# design.net
KiCad netlist of a schematic drawn in Altium Designer
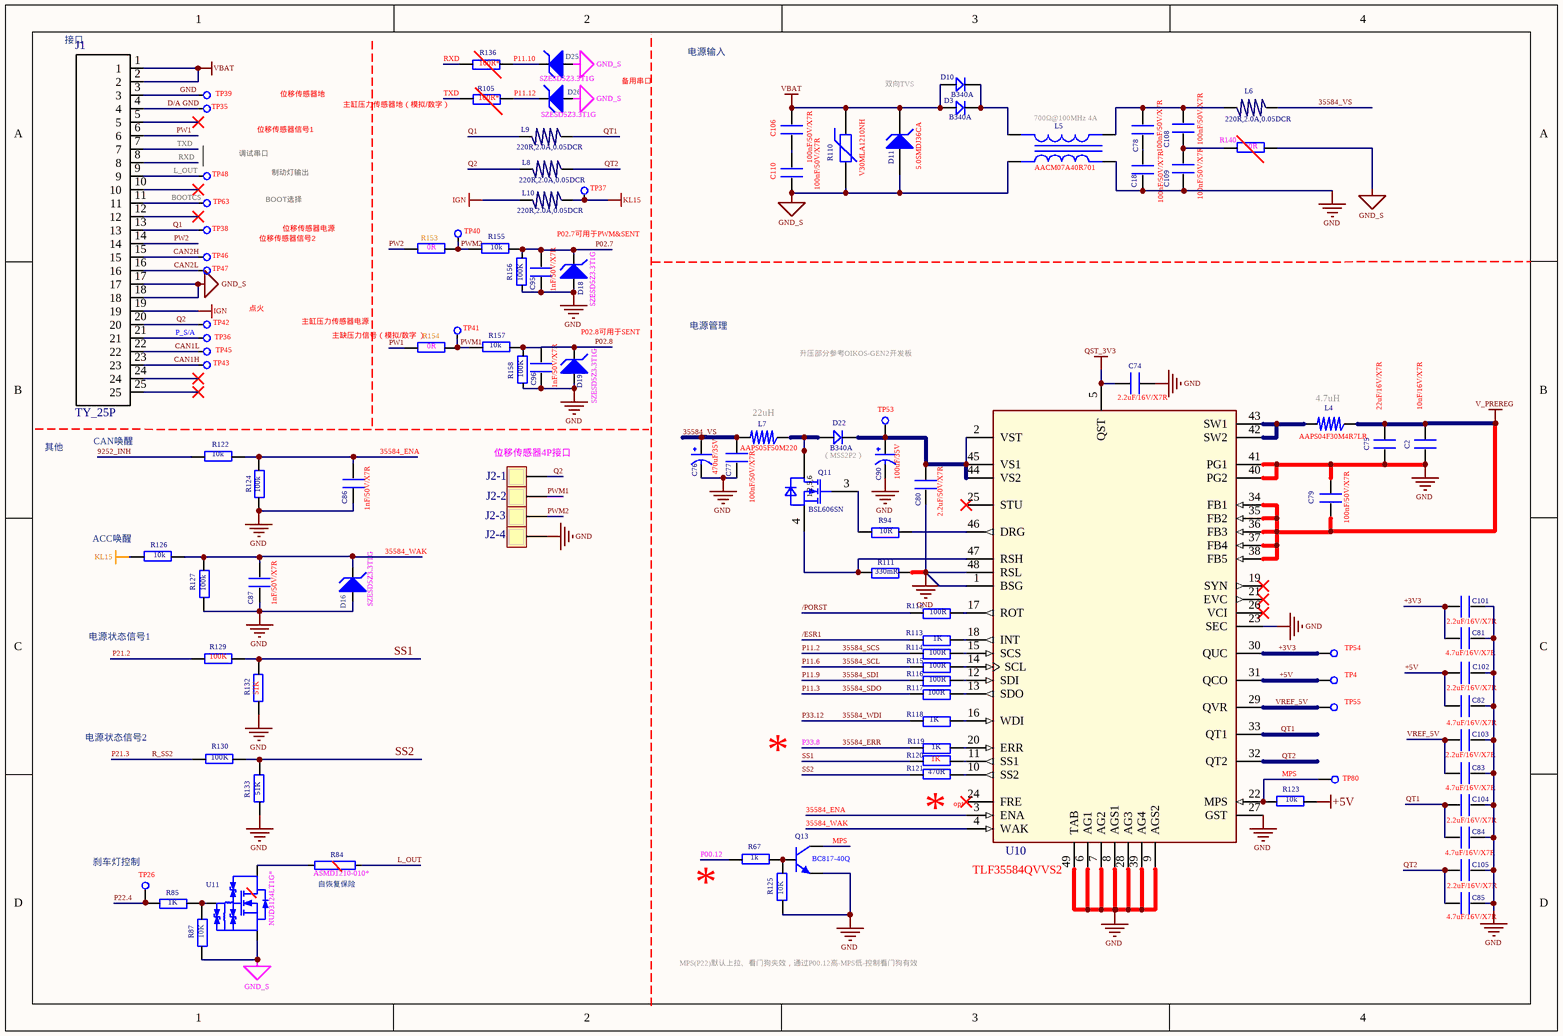
[diagram p0: 电源.SchDoc]

(export (version "E")
  (design (tool "Eeschema 10.0.6"))
  (components
    (comp (ref "C2")
      (value "10uF/16V/X7R")
      (footprint "C1206")
      (libsource (lib "WarShip V3 STM32103封装库") (part "C"))
    )
    (comp (ref "C18")
      (value "100nF/50V/X7R")
      (footprint "0805")
      (libsource (lib "WarShip V3 STM32103封装库") (part "C"))
    )
    (comp (ref "C74")
      (value "2.2uF/16V/X7R")
      (footprint "C0603P")
      (libsource (lib "WarShip V3 STM32103封装库") (part "C"))
    )
    (comp (ref "C75")
      (value "22uF/16V/X7R")
      (footprint "C1206")
      (libsource (lib "WarShip V3 STM32103封装库") (part "C"))
    )
    (comp (ref "C76")
      (value "470uF/35V")
      (footprint "CM F(10*10.2)")
      (libsource (lib "WarShip V3 STM32103封装库") (part "CAP"))
    )
    (comp (ref "C77")
      (value "100nF/50V/X7R")
      (footprint "C0603P")
      (libsource (lib "WarShip V3 STM32103封装库") (part "C"))
    )
    (comp (ref "C78")
      (value "100nF/50V/X7R")
      (footprint "0805")
      (libsource (lib "WarShip V3 STM32103封装库") (part "C"))
    )
    (comp (ref "C79")
      (value "100nF/50V/X7R")
      (footprint "C0603P")
      (libsource (lib "WarShip V3 STM32103封装库") (part "C"))
    )
    (comp (ref "C80")
      (value "2.2uF/50V/X7R")
      (footprint "C0805")
      (libsource (lib "WarShip V3 STM32103封装库") (part "C"))
    )
    (comp (ref "C81")
      (value "4.7uF/16V/X7R")
      (footprint "C0805")
      (libsource (lib "WarShip V3 STM32103封装库") (part "C"))
    )
    (comp (ref "C82")
      (value "4.7uF/16V/X7R")
      (footprint "C0805")
      (libsource (lib "WarShip V3 STM32103封装库") (part "C"))
    )
    (comp (ref "C83")
      (value "4.7uF/16V/X7R")
      (footprint "C0805")
      (libsource (lib "WarShip V3 STM32103封装库") (part "C"))
    )
    (comp (ref "C84")
      (value "4.7uF/16V/X7R")
      (footprint "C0805")
      (libsource (lib "WarShip V3 STM32103封装库") (part "C"))
    )
    (comp (ref "C85")
      (value "4.7uF/16V/X7R")
      (footprint "C0805")
      (libsource (lib "WarShip V3 STM32103封装库") (part "C"))
    )
    (comp (ref "C86")
      (value "1nF/50V/X7R")
      (footprint "C0603P")
      (libsource (lib "WarShip V3 STM32103封装库") (part "C"))
    )
    (comp (ref "C87")
      (value "1nF/50V/X7R")
      (footprint "C0603P")
      (libsource (lib "WarShip V3 STM32103封装库") (part "C"))
    )
    (comp (ref "C90")
      (value "100uF/35V")
      (footprint "AL-6.3*5.8")
      (libsource (lib "WarShip V3 STM32103封装库") (part "CAP"))
    )
    (comp (ref "C95")
      (value "1nF/50V/X7R")
      (footprint "C0603P")
      (libsource (lib "WarShip V3 STM32103封装库") (part "C"))
    )
    (comp (ref "C96")
      (value "1nF/50V/X7R")
      (footprint "C0603P")
      (libsource (lib "WarShip V3 STM32103封装库") (part "C"))
    )
    (comp (ref "C101")
      (value "2.2uF/16V/X7R")
      (footprint "C0603P")
      (libsource (lib "WarShip V3 STM32103封装库") (part "C"))
    )
    (comp (ref "C102")
      (value "2.2uF/16V/X7R")
      (footprint "C0603P")
      (libsource (lib "WarShip V3 STM32103封装库") (part "C"))
    )
    (comp (ref "C103")
      (value "2.2uF/16V/X7R")
      (footprint "C0603P")
      (libsource (lib "WarShip V3 STM32103封装库") (part "C"))
    )
    (comp (ref "C104")
      (value "2.2uF/16V/X7R")
      (footprint "C0603P")
      (libsource (lib "WarShip V3 STM32103封装库") (part "C"))
    )
    (comp (ref "C105")
      (value "2.2uF/16V/X7R")
      (footprint "C0603P")
      (libsource (lib "WarShip V3 STM32103封装库") (part "C"))
    )
    (comp (ref "C106")
      (value "100nF/50V/X7R")
      (footprint "0805")
      (libsource (lib "WarShip V3 STM32103封装库") (part "C"))
    )
    (comp (ref "C108")
      (value "100nF/50V/X7R")
      (footprint "C0805")
      (libsource (lib "WarShip V3 STM32103封装库") (part "C"))
    )
    (comp (ref "C109")
      (value "100nF/50V/X7R")
      (footprint "C0805")
      (libsource (lib "WarShip V3 STM32103封装库") (part "C"))
    )
    (comp (ref "C110")
      (value "100nF/50V/X7R")
      (footprint "0805")
      (libsource (lib "WarShip V3 STM32103封装库") (part "C"))
    )
    (comp (ref "D3")
      (value "B340A")
      (footprint "DO-214AC")
      (libsource (lib "WarShip V3 STM32103封装库") (part "D"))
    )
    (comp (ref "D10")
      (value "B340A")
      (footprint "DO-214AC")
      (libsource (lib "WarShip V3 STM32103封装库") (part "D"))
    )
    (comp (ref "D11")
      (value "5.0SMDJ36CA")
      (footprint "SMC_L6.9-W5.9-LS7.9-RD")
      (description "Zener Diode")
      (fields (field (name "PUBLISHER") "Altium Limited"))
      (libsource (lib "") (part "D Zener_1"))
    )
    (comp (ref "D16")
      (value "SZESD5Z3.3T1G")
      (footprint "SOD-523F")
      (description "Zener Diode")
      (fields (field (name "PUBLISHER") "Altium Limited"))
      (libsource (lib "Miscellaneous Devices") (part "D Zener"))
    )
    (comp (ref "D18")
      (value "SZESD5Z3.3T1G")
      (footprint "SOD-523F")
      (description "Zener Diode")
      (fields (field (name "PUBLISHER") "Altium Limited"))
      (libsource (lib "Miscellaneous Devices") (part "D Zener"))
    )
    (comp (ref "D19")
      (value "SZESD5Z3.3T1G")
      (footprint "SOD-523F")
      (description "Zener Diode")
      (fields (field (name "PUBLISHER") "Altium Limited"))
      (libsource (lib "Miscellaneous Devices") (part "D Zener"))
    )
    (comp (ref "D22")
      (value "B340A")
      (footprint "DO-214AC")
      (libsource (lib "WarShip V3 STM32103封装库") (part "D"))
    )
    (comp (ref "D25")
      (value "SZESD5Z3.3T1G")
      (footprint "SOD-523F")
      (description "Zener Diode")
      (fields (field (name "PUBLISHER") "Altium Limited"))
      (libsource (lib "Miscellaneous Devices") (part "D Zener"))
    )
    (comp (ref "D26")
      (value "SZESD5Z3.3T1G")
      (footprint "SOD-523F")
      (description "Zener Diode")
      (fields (field (name "PUBLISHER") "Altium Limited"))
      (libsource (lib "Miscellaneous Devices") (part "D Zener"))
    )
    (comp (ref "J1") (value "TY_25P") (footprint "TY421011") (libsource (lib "myTY") (part "TY_25P")))
    (comp (ref "J2-1")
      (value "pad")
      (footprint "焊盘")
      (description "单焊盘")
      (libsource (lib "myTY_NEW") (part "pad"))
    )
    (comp (ref "J2-2")
      (value "pad")
      (footprint "焊盘")
      (description "单焊盘")
      (libsource (lib "myTY_NEW") (part "pad"))
    )
    (comp (ref "J2-3")
      (value "pad")
      (footprint "焊盘")
      (description "单焊盘")
      (libsource (lib "myTY_NEW") (part "pad"))
    )
    (comp (ref "J2-4")
      (value "pad")
      (footprint "焊盘")
      (description "单焊盘")
      (libsource (lib "myTY_NEW") (part "pad"))
    )
    (comp (ref "L4")
      (value "AAPS04F30M4R7LR")
      (footprint "IND-SMD_L4.0-W4.0")
      (libsource (lib "WarShip V3 STM32103封装库") (part "L_SOP"))
    )
    (comp (ref "L5")
      (value "AACM07A40R701")
      (footprint "FILTER-SMD_4P-L7.0-W6.0-BL")
      (libsource (lib "zs_lib_wgs") (part "ACT45B-510-2P"))
    )
    (comp (ref "L6")
      (value "220R,2.0A,0.05DCR")
      (footprint "0603P")
      (libsource (lib "WarShip V3 STM32103封装库") (part "L"))
    )
    (comp (ref "L7")
      (value "AAPS05F50M220")
      (footprint "IND-SMD_L5.0-W5.0")
      (libsource (lib "WarShip V3 STM32103封装库") (part "L_SOP"))
    )
    (comp (ref "L8")
      (value "220R,2.0A,0.05DCR")
      (footprint "0603P")
      (libsource (lib "WarShip V3 STM32103封装库") (part "L"))
    )
    (comp (ref "L9")
      (value "220R,2.0A,0.05DCR")
      (footprint "0603P")
      (libsource (lib "WarShip V3 STM32103封装库") (part "L"))
    )
    (comp (ref "L10")
      (value "220R,2.0A,0.05DCR")
      (footprint "0603P")
      (libsource (lib "WarShip V3 STM32103封装库") (part "L"))
    )
    (comp (ref "Q11")
      (value "BSL606SN")
      (footprint "SOP95P250X110-6N")
      (fields (field (name "MANUFACTURER") "Infineon Technologies"))
      (libsource (lib "yds") (part "BSL606SN"))
    )
    (comp (ref "Q13")
      (value "BC817-40Q")
      (footprint "SOT-23N")
      (description "贴片三极管")
      (libsource (lib "myTY_NEW") (part "M_NPN"))
    )
    (comp (ref "R67") (value "1k") (footprint "0603P") (libsource (lib "") (part "R_1")))
    (comp (ref "R84")
      (value "ASMD1210-010*")
      (footprint "1210G")
      (description "自恢复保险")
      (libsource (lib "*") (part "RES2"))
    )
    (comp (ref "R85") (value "1K") (footprint "0603P") (libsource (lib "") (part "R_1")))
    (comp (ref "R87") (value "10K") (footprint "0603P") (libsource (lib "") (part "R_1")))
    (comp (ref "R94") (value "10R") (footprint "0603P") (libsource (lib "") (part "R_1")))
    (comp (ref "R105") (value "100R*") (footprint "0603P") (libsource (lib "") (part "R_1")))
    (comp (ref "R110")
      (value "V30MLA1210NH")
      (footprint "1210G")
      (description "Varistor (Voltage-Sensitive Resistor)")
      (fields (field (name "PUBLISHER") "Altium Limited"))
      (libsource (lib "Miscellaneous Devices") (part "Res Varistor"))
    )
    (comp (ref "R111") (value "330mR") (footprint "R2512") (libsource (lib "") (part "R_2")))
    (comp (ref "R112") (value "100R") (footprint "0603P") (libsource (lib "") (part "R_1")))
    (comp (ref "R113") (value "1K") (footprint "0603P") (libsource (lib "") (part "R_1")))
    (comp (ref "R114") (value "100R") (footprint "0603P") (libsource (lib "") (part "R_1")))
    (comp (ref "R115") (value "100R") (footprint "0603P") (libsource (lib "") (part "R_1")))
    (comp (ref "R116") (value "100R") (footprint "0603P") (libsource (lib "") (part "R_1")))
    (comp (ref "R117") (value "100R") (footprint "0603P") (libsource (lib "") (part "R_1")))
    (comp (ref "R118") (value "1K") (footprint "0603P") (libsource (lib "") (part "R_1")))
    (comp (ref "R119") (value "1K") (footprint "0603P") (libsource (lib "") (part "R_1")))
    (comp (ref "R120") (value "1K") (footprint "0603P") (libsource (lib "") (part "R_1")))
    (comp (ref "R121") (value "470R") (footprint "0603P") (libsource (lib "") (part "R_1")))
    (comp (ref "R122") (value "10k") (footprint "0603P") (libsource (lib "") (part "R_1")))
    (comp (ref "R123") (value "10k") (footprint "0603P") (libsource (lib "") (part "R_1")))
    (comp (ref "R124") (value "100k") (footprint "0603P") (libsource (lib "") (part "R_1")))
    (comp (ref "R125") (value "10K") (footprint "0603P") (libsource (lib "") (part "R_1")))
    (comp (ref "R126") (value "10k") (footprint "0603P") (libsource (lib "") (part "R_1")))
    (comp (ref "R127") (value "100k") (footprint "0603P") (libsource (lib "") (part "R_1")))
    (comp (ref "R129") (value "100K") (footprint "0603P") (libsource (lib "") (part "R_1")))
    (comp (ref "R130") (value "100K") (footprint "0603P") (libsource (lib "") (part "R_1")))
    (comp (ref "R132") (value "51K") (footprint "0603P") (libsource (lib "") (part "R_1")))
    (comp (ref "R133") (value "51K") (footprint "0603P") (libsource (lib "") (part "R_1")))
    (comp (ref "R136") (value "100R*") (footprint "0603P") (libsource (lib "") (part "R_1")))
    (comp (ref "R140") (value "*0R") (footprint "0603P") (libsource (lib "") (part "R_1")))
    (comp (ref "R153") (value "0R") (footprint "0603P") (libsource (lib "") (part "R_1")))
    (comp (ref "R154") (value "0R") (footprint "0603P") (libsource (lib "") (part "R_1")))
    (comp (ref "R155") (value "10k") (footprint "0603P") (libsource (lib "") (part "R_1")))
    (comp (ref "R156")
      (value "100K")
      (footprint "0603P")
      (libsource (lib "WarShip V3 STM32103封装库") (part "R"))
    )
    (comp (ref "R157") (value "10k") (footprint "0603P") (libsource (lib "") (part "R_1")))
    (comp (ref "R158")
      (value "100K")
      (footprint "0603P")
      (libsource (lib "WarShip V3 STM32103封装库") (part "R"))
    )
    (comp (ref "TP4") (value "测试点") (footprint "测试点") (libsource (lib "") (part "测试点_1")))
    (comp (ref "TP26") (value "测试点") (footprint "测试点") (libsource (lib "") (part "测试点_1")))
    (comp (ref "TP35") (value "测试点") (footprint "测试点") (libsource (lib "yds") (part "测试点")))
    (comp (ref "TP36") (value "测试点") (footprint "测试点") (libsource (lib "yds") (part "测试点")))
    (comp (ref "TP37") (value "测试点") (footprint "测试点") (libsource (lib "yds") (part "测试点")))
    (comp (ref "TP38") (value "测试点") (footprint "测试点") (libsource (lib "yds") (part "测试点")))
    (comp (ref "TP39") (value "测试点") (footprint "测试点") (libsource (lib "yds") (part "测试点")))
    (comp (ref "TP40") (value "测试点") (footprint "测试点") (libsource (lib "yds") (part "测试点")))
    (comp (ref "TP41") (value "测试点") (footprint "测试点") (libsource (lib "yds") (part "测试点")))
    (comp (ref "TP42") (value "测试点") (footprint "测试点") (libsource (lib "yds") (part "测试点")))
    (comp (ref "TP43") (value "测试点") (footprint "测试点") (libsource (lib "yds") (part "测试点")))
    (comp (ref "TP45") (value "测试点") (footprint "测试点") (libsource (lib "yds") (part "测试点")))
    (comp (ref "TP46") (value "测试点") (footprint "测试点") (libsource (lib "yds") (part "测试点")))
    (comp (ref "TP47") (value "测试点") (footprint "测试点") (libsource (lib "yds") (part "测试点")))
    (comp (ref "TP48") (value "测试点") (footprint "测试点") (libsource (lib "yds") (part "测试点")))
    (comp (ref "TP53") (value "测试点") (footprint "测试点") (libsource (lib "") (part "测试点_1")))
    (comp (ref "TP54") (value "测试点") (footprint "测试点") (libsource (lib "") (part "测试点_1")))
    (comp (ref "TP55") (value "测试点") (footprint "测试点") (libsource (lib "") (part "测试点_1")))
    (comp (ref "TP63") (value "测试点") (footprint "测试点") (libsource (lib "yds") (part "测试点")))
    (comp (ref "TP80") (value "测试点") (footprint "测试点") (libsource (lib "") (part "测试点_1")))
    (comp (ref "U10")
      (value "TLF35584QVVS2")
      (footprint "QFN50P700X700X90-49N-3-1")
      (description "Multi Voltage Safety Micro Processor Supply (5.0 V Variant)")
      (fields
        (field (name "MANUFACTURERPARTNUMBER") "TLF35584QVVS1")
        (field (name "MANUFACTURER") "Infineon Technologies")
      )
      (libsource (lib "yds") (part "TLF35584QVVS1"))
    )
    (comp (ref "U11")
      (value "NUD3124LT1G*")
      (footprint "SOT-23-NUD3124")
      (description "集成驱动器")
      (libsource (lib "myTY_NEW") (part "NUD3124"))
    )
  )
  (nets
    (net (code "1") (name "+5V") (class "Default")
      (node (ref "C102") (pin "2") (pintype "passive"))
      (node (ref "C82") (pin "2") (pintype "passive"))
      (node (ref "R123") (pin "1") (pintype "passive"))
      (node (ref "TP4") (pin "1") (pinfunction "1_1") (pintype "passive"))
      (node (ref "U10") (pin "31") (pinfunction "QCO_31") (pintype "power_in"))
    )
    (net (code "2") (name "/+3V3") (class "Default")
      (node (ref "C101") (pin "2") (pintype "passive"))
      (node (ref "C81") (pin "2") (pintype "passive"))
      (node (ref "TP54") (pin "1") (pinfunction "1_1") (pintype "passive"))
      (node (ref "U10") (pin "30") (pinfunction "QUC_30") (pintype "power_in"))
    )
    (net (code "3") (name "/9252_INH") (class "Default") (node (ref "R122") (pin "2") (pintype "passive")))
    (net (code "4") (name "/35584_ENA") (class "Default")
      (node (ref "C86") (pin "2") (pintype "passive"))
      (node (ref "R122") (pin "1") (pintype "passive"))
      (node (ref "R124") (pin "2") (pintype "passive"))
      (node (ref "U10") (pin "3") (pinfunction "ENA_3") (pintype "input"))
    )
    (net (code "5") (name "/35584_ERR") (class "Default") (node (ref "R119") (pin "1") (pintype "passive")))
    (net (code "6") (name "/35584_SCL") (class "Default") (node (ref "R115") (pin "1") (pintype "passive")))
    (net (code "7") (name "/35584_SCS") (class "Default") (node (ref "R114") (pin "1") (pintype "passive")))
    (net (code "8") (name "/35584_SDI") (class "Default") (node (ref "R116") (pin "1") (pintype "passive")))
    (net (code "9") (name "/35584_SDO") (class "Default") (node (ref "R117") (pin "1") (pintype "passive")))
    (net (code "10") (name "/35584_VS") (class "Default")
      (node (ref "C76") (pin "1") (pinfunction "VCC_1") (pintype "passive"))
      (node (ref "C77") (pin "2") (pintype "passive"))
      (node (ref "L6") (pin "1") (pintype "passive"))
      (node (ref "L7") (pin "2") (pinfunction "2_2") (pintype "passive"))
    )
    (net (code "11") (name "/35584_WAK") (class "Default")
      (node (ref "C87") (pin "2") (pintype "passive"))
      (node (ref "D16") (pin "1") (pinfunction "K_1") (pintype "passive"))
      (node (ref "R126") (pin "1") (pintype "passive"))
      (node (ref "R127") (pin "2") (pintype "passive"))
      (node (ref "U10") (pin "4") (pinfunction "WAK_4") (pintype "input"))
    )
    (net (code "12") (name "/35584_WDI") (class "Default") (node (ref "R118") (pin "1") (pintype "passive")))
    (net (code "13") (name "/BOOTCS") (class "Default")
      (node (ref "J1") (pin "11") (pinfunction "11_11") (pintype "passive"))
      (node (ref "TP63") (pin "1") (pinfunction "1_1") (pintype "passive"))
    )
    (net (code "14") (name "/CAN1H") (class "Default")
      (node (ref "J1") (pin "23") (pinfunction "23_23") (pintype "passive"))
      (node (ref "TP43") (pin "1") (pinfunction "1_1") (pintype "passive"))
    )
    (net (code "15") (name "/CAN1L") (class "Default")
      (node (ref "J1") (pin "22") (pinfunction "22_22") (pintype "passive"))
      (node (ref "TP45") (pin "1") (pinfunction "1_1") (pintype "passive"))
    )
    (net (code "16") (name "/CAN2H") (class "Default")
      (node (ref "J1") (pin "15") (pinfunction "15_15") (pintype "passive"))
      (node (ref "TP46") (pin "1") (pinfunction "1_1") (pintype "passive"))
    )
    (net (code "17") (name "/CAN2L") (class "Default")
      (node (ref "J1") (pin "16") (pinfunction "16_16") (pintype "passive"))
      (node (ref "TP47") (pin "1") (pinfunction "1_1") (pintype "passive"))
    )
    (net (code "18") (name "/D{slash}A GND") (class "Default")
      (node (ref "J1") (pin "4") (pinfunction "4_4") (pintype "passive"))
      (node (ref "TP35") (pin "1") (pinfunction "1_1") (pintype "passive"))
    )
    (net (code "19") (name "/L_OUT") (class "Default")
      (node (ref "J1") (pin "9") (pinfunction "9_9") (pintype "passive"))
      (node (ref "R84") (pin "2") (pinfunction "2_2") (pintype "passive"))
      (node (ref "TP48") (pin "1") (pinfunction "1_1") (pintype "passive"))
    )
    (net (code "20") (name "/MPS") (class "Default")
      (node (ref "Q13") (pin "2") (pinfunction "C_2") (pintype "passive"))
      (node (ref "R123") (pin "2") (pintype "passive"))
      (node (ref "TP80") (pin "1") (pinfunction "1_1") (pintype "passive"))
      (node (ref "U10") (pin "22") (pinfunction "MPS_22") (pintype "input"))
    )
    (net (code "21") (name "/P00.12") (class "Default") (node (ref "R67") (pin "2") (pintype "passive")))
    (net (code "22") (name "/P02.7") (class "Default")
      (node (ref "C95") (pin "2") (pintype "passive"))
      (node (ref "D18") (pin "1") (pinfunction "K_1") (pintype "passive"))
      (node (ref "R155") (pin "1") (pintype "passive"))
      (node (ref "R156") (pin "1") (pintype "passive"))
    )
    (net (code "23") (name "/P02.8") (class "Default")
      (node (ref "C96") (pin "2") (pintype "passive"))
      (node (ref "D19") (pin "1") (pinfunction "K_1") (pintype "passive"))
      (node (ref "R157") (pin "1") (pintype "passive"))
      (node (ref "R158") (pin "1") (pintype "passive"))
    )
    (net (code "24") (name "/P11.10") (class "Default")
      (node (ref "D25") (pin "1") (pinfunction "K_1") (pintype "passive"))
      (node (ref "R136") (pin "2") (pintype "passive"))
    )
    (net (code "25") (name "/P11.12") (class "Default")
      (node (ref "D26") (pin "1") (pinfunction "K_1") (pintype "passive"))
      (node (ref "R105") (pin "2") (pintype "passive"))
    )
    (net (code "26") (name "/P21.2") (class "Default") (node (ref "R129") (pin "2") (pintype "passive")))
    (net (code "27") (name "/P21.3") (class "Default") (node (ref "R130") (pin "2") (pintype "passive")))
    (net (code "28") (name "/P22.4") (class "Default")
      (node (ref "R85") (pin "1") (pintype "passive"))
      (node (ref "TP26") (pin "1") (pinfunction "1_1") (pintype "passive"))
    )
    (net (code "29") (name "/PW1") (class "Default")
      (node (ref "J1") (pin "6") (pinfunction "6_6") (pintype "passive"))
      (node (ref "R154") (pin "2") (pintype "passive"))
    )
    (net (code "30") (name "/PW2") (class "Default")
      (node (ref "J1") (pin "14") (pinfunction "14_14") (pintype "passive"))
      (node (ref "R153") (pin "2") (pintype "passive"))
    )
    (net (code "31") (name "/PWM1") (class "Default")
      (node (ref "J2-2") (pin "1") (pinfunction "1_1") (pintype "passive"))
      (node (ref "R154") (pin "1") (pintype "passive"))
      (node (ref "R157") (pin "2") (pintype "passive"))
      (node (ref "TP41") (pin "1") (pinfunction "1_1") (pintype "passive"))
    )
    (net (code "32") (name "/PWM2") (class "Default")
      (node (ref "J2-3") (pin "1") (pinfunction "1_1") (pintype "passive"))
      (node (ref "R153") (pin "1") (pintype "passive"))
      (node (ref "R155") (pin "2") (pintype "passive"))
      (node (ref "TP40") (pin "1") (pinfunction "1_1") (pintype "passive"))
    )
    (net (code "33") (name "/P_S{slash}A") (class "Default")
      (node (ref "J1") (pin "21") (pinfunction "21_21") (pintype "passive"))
      (node (ref "TP36") (pin "1") (pinfunction "1_1") (pintype "passive"))
    )
    (net (code "34") (name "/Q1") (class "Default")
      (node (ref "J1") (pin "13") (pinfunction "13_13") (pintype "passive"))
      (node (ref "L9") (pin "2") (pintype "passive"))
      (node (ref "TP38") (pin "1") (pinfunction "1_1") (pintype "passive"))
    )
    (net (code "35") (name "/Q2") (class "Default")
      (node (ref "J1") (pin "20") (pinfunction "20_20") (pintype "passive"))
      (node (ref "J2-1") (pin "1") (pinfunction "1_1") (pintype "passive"))
      (node (ref "L8") (pin "2") (pintype "passive"))
      (node (ref "TP42") (pin "1") (pinfunction "1_1") (pintype "passive"))
    )
    (net (code "36") (name "/QT1") (class "Default")
      (node (ref "C104") (pin "2") (pintype "passive"))
      (node (ref "C84") (pin "2") (pintype "passive"))
      (node (ref "L9") (pin "1") (pintype "passive"))
      (node (ref "U10") (pin "33") (pinfunction "QT1_33") (pintype "passive"))
    )
    (net (code "37") (name "/QT2") (class "Default")
      (node (ref "C105") (pin "2") (pintype "passive"))
      (node (ref "C85") (pin "2") (pintype "passive"))
      (node (ref "L8") (pin "1") (pintype "passive"))
      (node (ref "U10") (pin "32") (pinfunction "QT2_32") (pintype "passive"))
    )
    (net (code "38") (name "/RXD") (class "Default")
      (node (ref "J1") (pin "8") (pinfunction "8_8") (pintype "passive"))
      (node (ref "R136") (pin "1") (pintype "passive"))
    )
    (net (code "39") (name "/SS1") (class "Default")
      (node (ref "R120") (pin "2") (pintype "passive"))
      (node (ref "R129") (pin "1") (pintype "passive"))
      (node (ref "R132") (pin "1") (pintype "passive"))
    )
    (net (code "40") (name "/SS2") (class "Default")
      (node (ref "R121") (pin "2") (pintype "passive"))
      (node (ref "R130") (pin "1") (pintype "passive"))
      (node (ref "R133") (pin "1") (pintype "passive"))
    )
    (net (code "41") (name "/TXD") (class "Default")
      (node (ref "J1") (pin "7") (pinfunction "7_7") (pintype "passive"))
      (node (ref "R105") (pin "1") (pintype "passive"))
    )
    (net (code "42") (name "/VREF_5V") (class "Default")
      (node (ref "C103") (pin "2") (pintype "passive"))
      (node (ref "C83") (pin "2") (pintype "passive"))
      (node (ref "TP55") (pin "1") (pinfunction "1_1") (pintype "passive"))
      (node (ref "U10") (pin "29") (pinfunction "QVR_29") (pintype "power_in"))
    )
    (net (code "43") (name "/{slash}ESR1") (class "Default")
      (node (ref "R113") (pin "1") (pintype "passive"))
    )
    (net (code "44") (name "/{slash}PORST") (class "Default")
      (node (ref "R112") (pin "1") (pintype "passive"))
    )
    (net (code "45") (name "GND") (class "Default")
      (node (ref "C101") (pin "1") (pintype "passive"))
      (node (ref "C102") (pin "1") (pintype "passive"))
      (node (ref "C103") (pin "1") (pintype "passive"))
      (node (ref "C104") (pin "1") (pintype "passive"))
      (node (ref "C105") (pin "1") (pintype "passive"))
      (node (ref "C109") (pin "1") (pintype "passive"))
      (node (ref "C18") (pin "1") (pintype "passive"))
      (node (ref "C2") (pin "1") (pintype "passive"))
      (node (ref "C74") (pin "1") (pintype "passive"))
      (node (ref "C75") (pin "1") (pintype "passive"))
      (node (ref "C76") (pin "2") (pinfunction "GND_2") (pintype "passive"))
      (node (ref "C77") (pin "1") (pintype "passive"))
      (node (ref "C79") (pin "2") (pintype "passive"))
      (node (ref "C80") (pin "1") (pintype "passive"))
      (node (ref "C81") (pin "1") (pintype "passive"))
      (node (ref "C82") (pin "1") (pintype "passive"))
      (node (ref "C83") (pin "1") (pintype "passive"))
      (node (ref "C84") (pin "1") (pintype "passive"))
      (node (ref "C85") (pin "1") (pintype "passive"))
      (node (ref "C86") (pin "1") (pintype "passive"))
      (node (ref "C87") (pin "1") (pintype "passive"))
      (node (ref "C90") (pin "2") (pinfunction "GND_2") (pintype "passive"))
      (node (ref "C95") (pin "1") (pintype "passive"))
      (node (ref "C96") (pin "1") (pintype "passive"))
      (node (ref "D16") (pin "2") (pinfunction "A_2") (pintype "passive"))
      (node (ref "D18") (pin "2") (pinfunction "A_2") (pintype "passive"))
      (node (ref "D19") (pin "2") (pinfunction "A_2") (pintype "passive"))
      (node (ref "J1") (pin "3") (pinfunction "3_3") (pintype "passive"))
      (node (ref "J2-4") (pin "1") (pinfunction "1_1") (pintype "passive"))
      (node (ref "L5") (pin "4") (pinfunction "Pri-_4") (pintype "passive"))
      (node (ref "Q13") (pin "3") (pinfunction "E_3") (pintype "passive"))
      (node (ref "R111") (pin "1") (pintype "passive"))
      (node (ref "R124") (pin "1") (pintype "passive"))
      (node (ref "R125") (pin "2") (pintype "passive"))
      (node (ref "R127") (pin "1") (pintype "passive"))
      (node (ref "R132") (pin "2") (pintype "passive"))
      (node (ref "R133") (pin "2") (pintype "passive"))
      (node (ref "R156") (pin "2") (pintype "passive"))
      (node (ref "R158") (pin "2") (pintype "passive"))
      (node (ref "TP39") (pin "1") (pinfunction "1_1") (pintype "passive"))
      (node (ref "U10") (pin "1") (pinfunction "BSG_1") (pintype "power_in"))
      (node (ref "U10") (pin "23") (pinfunction "SEC_23") (pintype "passive"))
      (node (ref "U10") (pin "27") (pinfunction "GST_27") (pintype "passive"))
      (node (ref "U10") (pin "28") (pinfunction "AG3_28") (pintype "power_in"))
      (node (ref "U10") (pin "39") (pinfunction "AG4_39") (pintype "power_in"))
      (node (ref "U10") (pin "40") (pinfunction "PG2_40") (pintype "power_in"))
      (node (ref "U10") (pin "41") (pinfunction "PG1_41") (pintype "power_in"))
      (node (ref "U10") (pin "48") (pinfunction "RSL_48") (pintype "power_in"))
      (node (ref "U10") (pin "49") (pinfunction "TAB_49") (pintype "power_in"))
      (node (ref "U10") (pin "6") (pinfunction "AG1_6") (pintype "power_in"))
      (node (ref "U10") (pin "7") (pinfunction "AG2_7") (pintype "power_in"))
      (node (ref "U10") (pin "8") (pinfunction "AGS1_8") (pintype "power_in"))
      (node (ref "U10") (pin "9") (pinfunction "AGS2_9") (pintype "power_in"))
    )
    (net (code "46") (name "GND_S") (class "Default")
      (node (ref "C110") (pin "1") (pintype "passive"))
      (node (ref "D11") (pin "2") (pinfunction "K_2") (pintype "passive"))
      (node (ref "D25") (pin "2") (pinfunction "A_2") (pintype "passive"))
      (node (ref "D26") (pin "2") (pinfunction "A_2") (pintype "passive"))
      (node (ref "J1") (pin "17") (pinfunction "17_17") (pintype "passive"))
      (node (ref "J1") (pin "18") (pinfunction "18_18") (pintype "passive"))
      (node (ref "L5") (pin "1") (pinfunction "Pri+_1") (pintype "passive"))
      (node (ref "R110") (pin "2") (pinfunction "2_2") (pintype "passive"))
      (node (ref "R140") (pin "1") (pintype "passive"))
      (node (ref "R87") (pin "1") (pintype "passive"))
      (node (ref "U11") (pin "2") (pinfunction "S_2") (pintype "passive"))
    )
    (net (code "47") (name "IGN") (class "Default")
      (node (ref "J1") (pin "19") (pinfunction "19_19") (pintype "passive"))
      (node (ref "L10") (pin "2") (pintype "passive"))
    )
    (net (code "48") (name "KL15") (class "Default")
      (node (ref "L10") (pin "1") (pintype "passive"))
      (node (ref "R126") (pin "2") (pintype "passive"))
      (node (ref "TP37") (pin "1") (pinfunction "1_1") (pintype "passive"))
    )
    (net (code "49") (name "Net-(C18-Pad2)") (class "Default")
      (node (ref "C18") (pin "2") (pintype "passive"))
      (node (ref "C78") (pin "1") (pintype "passive"))
    )
    (net (code "50") (name "Net-(C90-VCC)") (class "Default")
      (node (ref "C80") (pin "2") (pintype "passive"))
      (node (ref "C90") (pin "1") (pinfunction "VCC_1") (pintype "passive"))
      (node (ref "D22") (pin "2") (pintype "passive"))
      (node (ref "TP53") (pin "1") (pinfunction "1_1") (pintype "passive"))
      (node (ref "U10") (pin "2") (pinfunction "VST_2") (pintype "power_in"))
      (node (ref "U10") (pin "44") (pinfunction "VS2_44") (pintype "power_in"))
      (node (ref "U10") (pin "45") (pinfunction "VS1_45") (pintype "power_in"))
    )
    (net (code "51") (name "Net-(C106-Pad1)") (class "Default")
      (node (ref "C106") (pin "1") (pintype "passive"))
      (node (ref "C110") (pin "2") (pintype "passive"))
    )
    (net (code "52") (name "Net-(C108-Pad1)") (class "Default")
      (node (ref "C108") (pin "1") (pintype "passive"))
      (node (ref "C109") (pin "2") (pintype "passive"))
      (node (ref "R140") (pin "2") (pintype "passive"))
    )
    (net (code "53") (name "Net-(D22-Pad1)") (class "Default")
      (node (ref "D22") (pin "1") (pintype "passive"))
      (node (ref "L7") (pin "1") (pinfunction "1_1") (pintype "passive"))
      (node (ref "Q11") (pin "1") (pinfunction "DRAIN_1") (pintype "passive"))
      (node (ref "Q11") (pin "2") (pinfunction "DRAIN_2") (pintype "passive"))
      (node (ref "Q11") (pin "5") (pinfunction "DRAIN_5") (pintype "passive"))
      (node (ref "Q11") (pin "6") (pinfunction "DRAIN_6") (pintype "passive"))
    )
    (net (code "54") (name "Net-(L5-Sec+)") (class "Default")
      (node (ref "D10") (pin "2") (pintype "passive"))
      (node (ref "D3") (pin "2") (pintype "passive"))
      (node (ref "L5") (pin "2") (pinfunction "Sec+_2") (pintype "passive"))
    )
    (net (code "55") (name "Net-(L5-Sec-)") (class "Default")
      (node (ref "C108") (pin "2") (pintype "passive"))
      (node (ref "C78") (pin "2") (pintype "passive"))
      (node (ref "L5") (pin "3") (pinfunction "Sec-_3") (pintype "passive"))
      (node (ref "L6") (pin "2") (pintype "passive"))
    )
    (net (code "56") (name "Net-(Q11-GATE)") (class "Default")
      (node (ref "Q11") (pin "3") (pinfunction "GATE_3") (pintype "passive"))
      (node (ref "R94") (pin "1") (pintype "passive"))
    )
    (net (code "57") (name "Net-(Q11-SOURCE)") (class "Default")
      (node (ref "Q11") (pin "4") (pinfunction "SOURCE_4") (pintype "passive"))
      (node (ref "R111") (pin "2") (pintype "passive"))
      (node (ref "U10") (pin "47") (pinfunction "RSH_47") (pintype "power_in"))
    )
    (net (code "58") (name "Net-(Q13-B)") (class "Default")
      (node (ref "Q13") (pin "1") (pinfunction "B_1") (pintype "passive"))
      (node (ref "R125") (pin "1") (pintype "passive"))
      (node (ref "R67") (pin "1") (pintype "passive"))
    )
    (net (code "59") (name "Net-(U10-DRG)") (class "Default")
      (node (ref "R94") (pin "2") (pintype "passive"))
      (node (ref "U10") (pin "46") (pinfunction "DRG_46") (pintype "output"))
    )
    (net (code "60") (name "Net-(U10-ERR)") (class "Default")
      (node (ref "R119") (pin "2") (pintype "passive"))
      (node (ref "U10") (pin "20") (pinfunction "ERR_20") (pintype "input"))
    )
    (net (code "61") (name "Net-(U10-INT)") (class "Default")
      (node (ref "R113") (pin "2") (pintype "passive"))
      (node (ref "U10") (pin "18") (pinfunction "INT_18") (pintype "output"))
    )
    (net (code "62") (name "Net-(U10-ROT)") (class "Default")
      (node (ref "R112") (pin "2") (pintype "passive"))
      (node (ref "U10") (pin "17") (pinfunction "ROT_17") (pintype "output"))
    )
    (net (code "63") (name "Net-(U10-SCL)") (class "Default")
      (node (ref "R115") (pin "2") (pintype "passive"))
      (node (ref "U10") (pin "14") (pinfunction "SCL_14") (pintype "input"))
    )
    (net (code "64") (name "Net-(U10-SCS)") (class "Default")
      (node (ref "R114") (pin "2") (pintype "passive"))
      (node (ref "U10") (pin "15") (pinfunction "SCS_15") (pintype "input"))
    )
    (net (code "65") (name "Net-(U10-SDI)") (class "Default")
      (node (ref "R116") (pin "2") (pintype "passive"))
      (node (ref "U10") (pin "12") (pinfunction "SDI_12") (pintype "input"))
    )
    (net (code "66") (name "Net-(U10-SDO)") (class "Default")
      (node (ref "R117") (pin "2") (pintype "passive"))
      (node (ref "U10") (pin "13") (pinfunction "SDO_13") (pintype "output"))
    )
    (net (code "67") (name "Net-(U10-SS1)") (class "Default")
      (node (ref "R120") (pin "1") (pintype "passive"))
      (node (ref "U10") (pin "11") (pinfunction "SS1_11") (pintype "output"))
    )
    (net (code "68") (name "Net-(U10-SS2)") (class "Default")
      (node (ref "R121") (pin "1") (pintype "passive"))
      (node (ref "U10") (pin "10") (pinfunction "SS2_10") (pintype "output"))
    )
    (net (code "69") (name "Net-(U10-SW1)") (class "Default")
      (node (ref "L4") (pin "2") (pinfunction "2_2") (pintype "passive"))
      (node (ref "U10") (pin "42") (pinfunction "SW2_42") (pintype "power_in"))
      (node (ref "U10") (pin "43") (pinfunction "SW1_43") (pintype "power_in"))
    )
    (net (code "70") (name "Net-(U10-WDI)") (class "Default")
      (node (ref "R118") (pin "2") (pintype "passive"))
      (node (ref "U10") (pin "16") (pinfunction "WDI_16") (pintype "input"))
    )
    (net (code "71") (name "Net-(U11-D)") (class "Default")
      (node (ref "R84") (pin "1") (pinfunction "1_1") (pintype "passive"))
      (node (ref "U11") (pin "3") (pinfunction "D_3") (pintype "passive"))
    )
    (net (code "72") (name "Net-(U11-G)") (class "Default")
      (node (ref "R85") (pin "2") (pintype "passive"))
      (node (ref "R87") (pin "2") (pintype "passive"))
      (node (ref "U11") (pin "1") (pinfunction "G_1") (pintype "passive"))
    )
    (net (code "73") (name "QST_3V3") (class "Default")
      (node (ref "C74") (pin "2") (pintype "passive"))
      (node (ref "U10") (pin "5") (pinfunction "QST_5") (pintype "power_in"))
    )
    (net (code "74") (name "VBAT") (class "Default")
      (node (ref "C106") (pin "2") (pintype "passive"))
      (node (ref "D10") (pin "1") (pintype "passive"))
      (node (ref "D11") (pin "1") (pinfunction "A_1") (pintype "passive"))
      (node (ref "D3") (pin "1") (pintype "passive"))
      (node (ref "J1") (pin "1") (pinfunction "1_1") (pintype "passive"))
      (node (ref "J1") (pin "2") (pinfunction "2_2") (pintype "passive"))
      (node (ref "R110") (pin "1") (pinfunction "1_1") (pintype "passive"))
    )
    (net (code "75") (name "V_PREREG") (class "Default")
      (node (ref "C2") (pin "2") (pintype "passive"))
      (node (ref "C75") (pin "2") (pintype "passive"))
      (node (ref "C79") (pin "1") (pintype "passive"))
      (node (ref "L4") (pin "1") (pinfunction "1_1") (pintype "passive"))
      (node (ref "U10") (pin "34") (pinfunction "FB1_34") (pintype "input"))
      (node (ref "U10") (pin "35") (pinfunction "FB2_35") (pintype "input"))
      (node (ref "U10") (pin "36") (pinfunction "FB3_36") (pintype "input"))
      (node (ref "U10") (pin "37") (pinfunction "FB4_37") (pintype "input"))
      (node (ref "U10") (pin "38") (pinfunction "FB5_38") (pintype "input"))
    )
    (net (code "76") (name "unconnected-(J1-Pad5)") (class "Default")
      (node (ref "J1") (pin "5") (pinfunction "5_5") (pintype "passive+no_connect"))
    )
    (net (code "77") (name "unconnected-(J1-Pad10)") (class "Default")
      (node (ref "J1") (pin "10") (pinfunction "10_10") (pintype "passive+no_connect"))
    )
    (net (code "78") (name "unconnected-(J1-Pad12)") (class "Default")
      (node (ref "J1") (pin "12") (pinfunction "12_12") (pintype "passive+no_connect"))
    )
    (net (code "79") (name "unconnected-(J1-Pad24)") (class "Default")
      (node (ref "J1") (pin "24") (pinfunction "24_24") (pintype "passive+no_connect"))
    )
    (net (code "80") (name "unconnected-(J1-Pad25)") (class "Default")
      (node (ref "J1") (pin "25") (pinfunction "25_25") (pintype "passive+no_connect"))
    )
    (net (code "81") (name "unconnected-(U10-EVC-Pad21)") (class "Default")
      (node (ref "U10") (pin "21") (pinfunction "EVC_21") (pintype "output+no_connect"))
    )
    (net (code "82") (name "unconnected-(U10-FRE-Pad24)") (class "Default")
      (node (ref "U10") (pin "24") (pinfunction "FRE_24") (pintype "passive+no_connect"))
    )
    (net (code "83") (name "unconnected-(U10-STU-Pad25)") (class "Default")
      (node (ref "U10") (pin "25") (pinfunction "STU_25") (pintype "passive+no_connect"))
    )
    (net (code "84") (name "unconnected-(U10-SYN-Pad19)") (class "Default")
      (node (ref "U10") (pin "19") (pinfunction "SYN_19") (pintype "output+no_connect"))
    )
    (net (code "85") (name "unconnected-(U10-VCI-Pad26)") (class "Default")
      (node (ref "U10") (pin "26") (pinfunction "VCI_26") (pintype "power_in+no_connect"))
    )
  )
)
